# Sheet1.net
KiCad netlist of a schematic drawn in Altium Designer
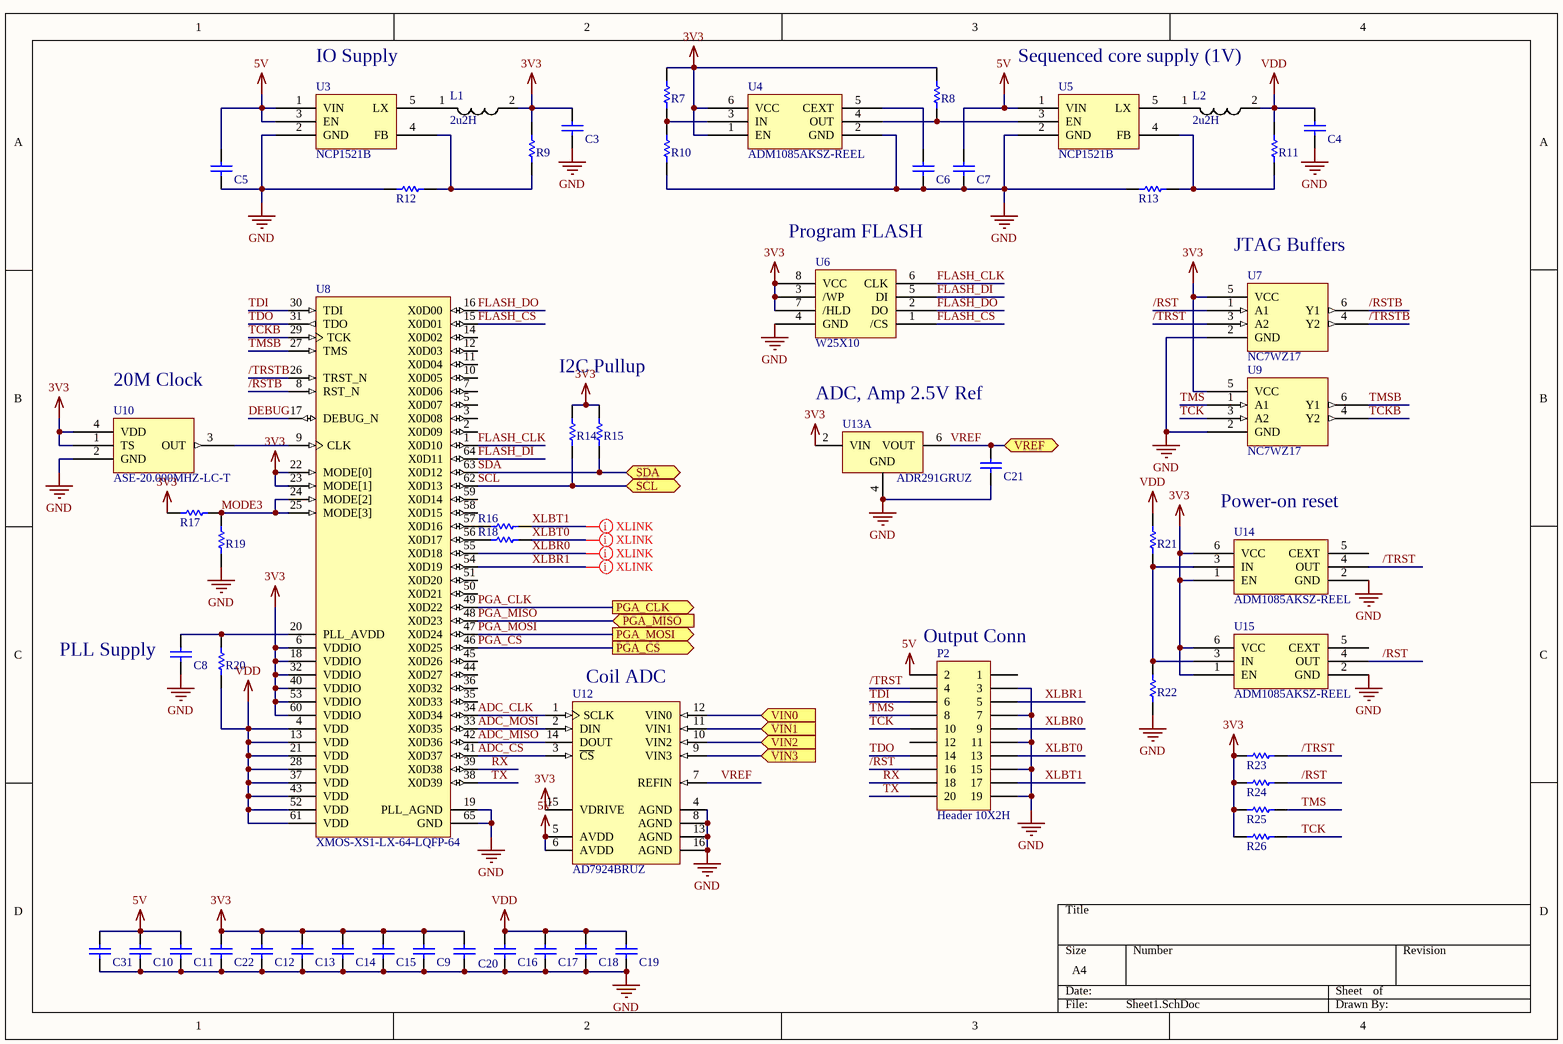
[diagram p0: Sheet1.SchDoc]

(export (version "E")
  (design (tool "Eeschema 10.0.6"))
  (components
    (comp (ref "C3")
      (value "CAP 10uF 6.3V 0603(1608)")
      (footprint "CAPC0603(1608)100_N")
      (description "CAP 10uF 6.3V ±20% 0603 (1608 Metric) Thickness 1mm SMD")
      (fields (field (name "TOLERANCE") "±20%"))
      (libsource (lib "Altium Content Vault") (part "CMP-1035-02797-1"))
    )
    (comp (ref "C4")
      (value "CAP 10uF 6.3V 0603(1608)")
      (footprint "CAPC0603(1608)100_N")
      (description "CAP 10uF 6.3V ±20% 0603 (1608 Metric) Thickness 1mm SMD")
      (fields (field (name "TOLERANCE") "±20%"))
      (libsource (lib "Altium Content Vault") (part "CMP-1035-02797-1"))
    )
    (comp (ref "C5")
      (value "CAP 10uF 6.3V 0603(1608)")
      (footprint "CAPC0603(1608)100_N")
      (description "CAP 10uF 6.3V ±20% 0603 (1608 Metric) Thickness 1mm SMD")
      (fields (field (name "TOLERANCE") "±20%"))
      (libsource (lib "Altium Content Vault") (part "CMP-1035-02797-1"))
    )
    (comp (ref "C6")
      (value "CAP 10nF 10V 0402(1005)")
      (footprint "CAPC0402(1005)60_N")
      (description "CAP 10nF 10V ±5% 0402 (1005 Metric) Thickness 0.6mm SMD")
      (fields (field (name "TOLERANCE") "±5%"))
      (libsource (lib "Altium Content Vault") (part "CMP-1034-01870-1"))
    )
    (comp (ref "C7")
      (value "CAP 10uF 6.3V 0603(1608)")
      (footprint "CAPC0603(1608)100_N")
      (description "CAP 10uF 6.3V ±20% 0603 (1608 Metric) Thickness 1mm SMD")
      (fields (field (name "TOLERANCE") "±20%"))
      (libsource (lib "Altium Content Vault") (part "CMP-1035-02797-1"))
    )
    (comp (ref "C8")
      (value "CAP 1uF 16V 0402(1005)")
      (footprint "CAPC0402(1005)60_N")
      (description "CAP 1uF 16V ±20% 0402 (1005 Metric) Thickness 0.6mm SMD")
      (fields (field (name "TOLERANCE") "±20%"))
      (libsource (lib "Altium Content Vault") (part "CMP-1034-02120-1"))
    )
    (comp (ref "C9")
      (value "CAP 100nF 25V 0402(1005)")
      (footprint "CAPC0402(1005)60_N")
      (description "CAP 100nF 25V ±20% 0402 (1005 Metric) Thickness 0.6mm SMD")
      (fields (field (name "TOLERANCE") "±20%"))
      (libsource (lib "Altium Content Vault") (part "CMP-1034-02073-1"))
    )
    (comp (ref "C10")
      (value "CAP 100nF 25V 0402(1005)")
      (footprint "CAPC0402(1005)60_N")
      (description "CAP 100nF 25V ±20% 0402 (1005 Metric) Thickness 0.6mm SMD")
      (fields (field (name "TOLERANCE") "±20%"))
      (libsource (lib "Altium Content Vault") (part "CMP-1034-02073-1"))
    )
    (comp (ref "C11")
      (value "CAP 100nF 25V 0402(1005)")
      (footprint "CAPC0402(1005)60_N")
      (description "CAP 100nF 25V ±20% 0402 (1005 Metric) Thickness 0.6mm SMD")
      (fields (field (name "TOLERANCE") "±20%"))
      (libsource (lib "Altium Content Vault") (part "CMP-1034-02073-1"))
    )
    (comp (ref "C12")
      (value "CAP 1uF 16V 0402(1005)")
      (footprint "CAPC0402(1005)60_N")
      (description "CAP 1uF 16V ±20% 0402 (1005 Metric) Thickness 0.6mm SMD")
      (fields (field (name "TOLERANCE") "±20%"))
      (libsource (lib "Altium Content Vault") (part "CMP-1034-02120-1"))
    )
    (comp (ref "C13")
      (value "CAP 1uF 16V 0402(1005)")
      (footprint "CAPC0402(1005)60_N")
      (description "CAP 1uF 16V ±20% 0402 (1005 Metric) Thickness 0.6mm SMD")
      (fields (field (name "TOLERANCE") "±20%"))
      (libsource (lib "Altium Content Vault") (part "CMP-1034-02120-1"))
    )
    (comp (ref "C14")
      (value "CAP 100nF 25V 0402(1005)")
      (footprint "CAPC0402(1005)60_N")
      (description "CAP 100nF 25V ±20% 0402 (1005 Metric) Thickness 0.6mm SMD")
      (fields (field (name "TOLERANCE") "±20%"))
      (libsource (lib "Altium Content Vault") (part "CMP-1034-02073-1"))
    )
    (comp (ref "C15")
      (value "CAP 100nF 25V 0402(1005)")
      (footprint "CAPC0402(1005)60_N")
      (description "CAP 100nF 25V ±20% 0402 (1005 Metric) Thickness 0.6mm SMD")
      (fields (field (name "TOLERANCE") "±20%"))
      (libsource (lib "Altium Content Vault") (part "CMP-1034-02073-1"))
    )
    (comp (ref "C16")
      (value "CAP 100nF 25V 0402(1005)")
      (footprint "CAPC0402(1005)60_N")
      (description "CAP 100nF 25V ±20% 0402 (1005 Metric) Thickness 0.6mm SMD")
      (fields (field (name "TOLERANCE") "±20%"))
      (libsource (lib "Altium Content Vault") (part "CMP-1034-02073-1"))
    )
    (comp (ref "C17")
      (value "CAP 100nF 25V 0402(1005)")
      (footprint "CAPC0402(1005)60_N")
      (description "CAP 100nF 25V ±20% 0402 (1005 Metric) Thickness 0.6mm SMD")
      (fields (field (name "TOLERANCE") "±20%"))
      (libsource (lib "Altium Content Vault") (part "CMP-1034-02073-1"))
    )
    (comp (ref "C18")
      (value "CAP 1uF 16V 0402(1005)")
      (footprint "CAPC0402(1005)60_N")
      (description "CAP 1uF 16V ±20% 0402 (1005 Metric) Thickness 0.6mm SMD")
      (fields (field (name "TOLERANCE") "±20%"))
      (libsource (lib "Altium Content Vault") (part "CMP-1034-02120-1"))
    )
    (comp (ref "C19")
      (value "CAP 1uF 16V 0402(1005)")
      (footprint "CAPC0402(1005)60_N")
      (description "CAP 1uF 16V ±20% 0402 (1005 Metric) Thickness 0.6mm SMD")
      (fields (field (name "TOLERANCE") "±20%"))
      (libsource (lib "Altium Content Vault") (part "CMP-1034-02120-1"))
    )
    (comp (ref "C20")
      (value "CAP 100nF 25V 0402(1005)")
      (footprint "CAPC0402(1005)60_N")
      (description "CAP 100nF 25V ±20% 0402 (1005 Metric) Thickness 0.6mm SMD")
      (fields (field (name "TOLERANCE") "±20%"))
      (libsource (lib "Altium Content Vault") (part "CMP-1034-02073-1"))
    )
    (comp (ref "C21")
      (value "CAP 100nF 25V 0402(1005)")
      (footprint "CAPC0402(1005)60_N")
      (description "CAP 100nF 25V ±20% 0402 (1005 Metric) Thickness 0.6mm SMD")
      (fields (field (name "TOLERANCE") "±20%"))
      (libsource (lib "Altium Content Vault") (part "CMP-1034-02073-1"))
    )
    (comp (ref "C22")
      (value "CAP 1uF 16V 0402(1005)")
      (footprint "CAPC0402(1005)60_N")
      (description "CAP 1uF 16V ±20% 0402 (1005 Metric) Thickness 0.6mm SMD")
      (fields (field (name "TOLERANCE") "±20%"))
      (libsource (lib "Altium Content Vault") (part "CMP-1034-02120-1"))
    )
    (comp (ref "C31")
      (value "CAP 10uF 6.3V 0603(1608)")
      (footprint "CAPC0603(1608)100_N")
      (description "CAP 10uF 6.3V ±20% 0603 (1608 Metric) Thickness 1mm SMD")
      (fields (field (name "TOLERANCE") "±20%"))
      (libsource (lib "Altium Content Vault") (part "CMP-1035-02797-1"))
    )
    (comp (ref "L1")
      (value "2u2H")
      (footprint "2016 Inductor")
      (libsource (lib "Centum") (part "2016 Inductor"))
    )
    (comp (ref "L2")
      (value "2u2H")
      (footprint "2016 Inductor")
      (libsource (lib "Centum") (part "2016 Inductor"))
    )
    (comp (ref "P2")
      (value "Header 10X2H")
      (footprint "HDR2X10H")
      (description "Header, 10-Pin, Dual row, Right Angle")
      (fields (field (name "PUBLISHER") "Altium Limited"))
      (libsource (lib "Miscellaneous Connectors") (part "Header 10X2H"))
    )
    (comp (ref "R7")
      (value "36K 1% 0402(1005)")
      (footprint "RESC0402(1005)_N")
      (description "36K 0.063W 1% 0402 (1005 Metric)  SMD")
      (fields (field (name "POWER") "0.063 W") (field (name "TOLERANCE") "1 %"))
      (libsource (lib "Altium Content Vault") (part "CMP-1011-00685-1"))
    )
    (comp (ref "R8")
      (value "10K 1% 0402(1005)")
      (footprint "RESC0402(1005)_N")
      (description "10K 0.063W 1% 0402 (1005 Metric)  SMD")
      (fields (field (name "TOLERANCE") "1 %") (field (name "POWER") "0.063 W"))
      (libsource (lib "Altium Content Vault") (part "CMP-1011-00623-1"))
    )
    (comp (ref "R9")
      (value "68K 1% 0402(1005)")
      (footprint "RESC0402(1005)_N")
      (description "68K 0.063W 1% 0402 (1005 Metric)  SMD")
      (fields (field (name "TOLERANCE") "1 %") (field (name "POWER") "0.063 W"))
      (libsource (lib "Altium Content Vault") (part "CMP-1011-00717-1"))
    )
    (comp (ref "R10")
      (value "10K 1% 0402(1005)")
      (footprint "RESC0402(1005)_N")
      (description "10K 0.063W 1% 0402 (1005 Metric)  SMD")
      (fields (field (name "TOLERANCE") "1 %") (field (name "POWER") "0.063 W"))
      (libsource (lib "Altium Content Vault") (part "CMP-1011-00623-1"))
    )
    (comp (ref "R11")
      (value "68K 1% 0402(1005)")
      (footprint "RESC0402(1005)_N")
      (description "68K 0.063W 1% 0402 (1005 Metric)  SMD")
      (fields (field (name "TOLERANCE") "1 %") (field (name "POWER") "0.063 W"))
      (libsource (lib "Altium Content Vault") (part "CMP-1011-00717-1"))
    )
    (comp (ref "R12")
      (value "15K 5% 0402(1005)")
      (footprint "RESC0402(1005)_N")
      (description "15K 0.063W 5% 0402 (1005 Metric)  SMD")
      (fields (field (name "TOLERANCE") "5 %") (field (name "POWER") "0.063 W"))
      (libsource (lib "Altium Content Vault") (part "RES"))
    )
    (comp (ref "R13")
      (value "100K 1% 0402(1005)")
      (footprint "RESC0402(1005)_N")
      (description "100K 0.063W 1% 0402 (1005 Metric)  SMD")
      (fields (field (name "POWER") "0.063 W") (field (name "TOLERANCE") "1 %"))
      (libsource (lib "Altium Content Vault") (part "CMP-1011-00736-1"))
    )
    (comp (ref "R14")
      (value "10K 1% 0402(1005)")
      (footprint "RESC0402(1005)_N")
      (description "10K 0.063W 1% 0402 (1005 Metric)  SMD")
      (fields (field (name "TOLERANCE") "1 %") (field (name "POWER") "0.063 W"))
      (libsource (lib "Altium Content Vault") (part "CMP-1011-00623-1"))
    )
    (comp (ref "R15")
      (value "10K 1% 0402(1005)")
      (footprint "RESC0402(1005)_N")
      (description "10K 0.063W 1% 0402 (1005 Metric)  SMD")
      (fields (field (name "TOLERANCE") "1 %") (field (name "POWER") "0.063 W"))
      (libsource (lib "Altium Content Vault") (part "CMP-1011-00623-1"))
    )
    (comp (ref "R16")
      (value "33R 5% 0402(1005)")
      (footprint "RESC0402(1005)_N")
      (description "33R 0.063W 5% 0402 (1005 Metric)  SMD")
      (fields (field (name "TOLERANCE") "5 %") (field (name "POWER") "0.063 W"))
      (libsource (lib "Altium Content Vault") (part "CMP-1011-00038-1"))
    )
    (comp (ref "R17")
      (value "10K 1% 0402(1005)")
      (footprint "RESC0402(1005)_N")
      (description "10K 0.063W 1% 0402 (1005 Metric)  SMD")
      (fields (field (name "TOLERANCE") "1 %") (field (name "POWER") "0.063 W"))
      (libsource (lib "Altium Content Vault") (part "CMP-1011-00623-1"))
    )
    (comp (ref "R18")
      (value "33R 5% 0402(1005)")
      (footprint "RESC0402(1005)_N")
      (description "33R 0.063W 5% 0402 (1005 Metric)  SMD")
      (fields (field (name "TOLERANCE") "5 %") (field (name "POWER") "0.063 W"))
      (libsource (lib "Altium Content Vault") (part "CMP-1011-00038-1"))
    )
    (comp (ref "R19")
      (value "Jumper 0402(1005)")
      (footprint "RESC0402(1005)_N")
      (description "Jumper 0402 (1005 Metric)")
      (fields (field (name "TOLERANCE") "None"))
      (libsource (lib "Altium Content Vault") (part "CMP-1011-00001-1"))
    )
    (comp (ref "R20")
      (value "4R7 5% 0402(1005)")
      (footprint "RESC0402(1005)_N")
      (description "4R7 0.063W 5% 0402 (1005 Metric)  SMD")
      (fields (field (name "POWER") "0.063 W") (field (name "TOLERANCE") "5 %"))
      (libsource (lib "Altium Content Vault") (part "CMP-1011-00018-1"))
    )
    (comp (ref "R21")
      (value "15K 1% 0402(1005)")
      (footprint "RESC0402(1005)_N")
      (description "15K 0.063W 1% 0402 (1005 Metric)  SMD")
      (fields (field (name "POWER") "0.063 W") (field (name "TOLERANCE") "1 %"))
      (libsource (lib "Altium Content Vault") (part "CMP-1011-00641-1"))
    )
    (comp (ref "R22")
      (value "36K 1% 0402(1005)")
      (footprint "RESC0402(1005)_N")
      (description "36K 0.063W 1% 0402 (1005 Metric)  SMD")
      (fields (field (name "POWER") "0.063 W") (field (name "TOLERANCE") "1 %"))
      (libsource (lib "Altium Content Vault") (part "CMP-1011-00685-1"))
    )
    (comp (ref "R23")
      (value "10K 1% 0402(1005)")
      (footprint "RESC0402(1005)_N")
      (description "10K 0.063W 1% 0402 (1005 Metric)  SMD")
      (fields (field (name "TOLERANCE") "1 %") (field (name "POWER") "0.063 W"))
      (libsource (lib "Altium Content Vault") (part "CMP-1011-00623-1"))
    )
    (comp (ref "R24")
      (value "10K 1% 0402(1005)")
      (footprint "RESC0402(1005)_N")
      (description "10K 0.063W 1% 0402 (1005 Metric)  SMD")
      (fields (field (name "TOLERANCE") "1 %") (field (name "POWER") "0.063 W"))
      (libsource (lib "Altium Content Vault") (part "CMP-1011-00623-1"))
    )
    (comp (ref "R25")
      (value "10K 1% 0402(1005)")
      (footprint "RESC0402(1005)_N")
      (description "10K 0.063W 1% 0402 (1005 Metric)  SMD")
      (fields (field (name "TOLERANCE") "1 %") (field (name "POWER") "0.063 W"))
      (libsource (lib "Altium Content Vault") (part "CMP-1011-00623-1"))
    )
    (comp (ref "R26")
      (value "10K 1% 0402(1005)")
      (footprint "RESC0402(1005)_N")
      (description "10K 0.063W 1% 0402 (1005 Metric)  SMD")
      (fields (field (name "TOLERANCE") "1 %") (field (name "POWER") "0.063 W"))
      (libsource (lib "Altium Content Vault") (part "CMP-1011-00623-1"))
    )
    (comp (ref "U3") (value "NCP1521B") (footprint "TSOP5") (libsource (lib "Centum") (part "NCP1521B")))
    (comp (ref "U4")
      (value "ADM1085AKSZ-REEL")
      (footprint "KS_6")
      (description "Imported")
      (libsource (lib "Centum") (part "ADM1085AKSZ-REEL"))
    )
    (comp (ref "U5") (value "NCP1521B") (footprint "TSOP5") (libsource (lib "Centum") (part "NCP1521B")))
    (comp (ref "U6") (value "W25X10") (footprint "SO8_N") (libsource (lib "Centum") (part "W25X10")))
    (comp (ref "U7") (value "NC7WZ17") (footprint "KS_6") (libsource (lib "Centum") (part "NC7WZ17")))
    (comp (ref "U8")
      (value "XMOS-XS1-LX-64-LQFP-64")
      (footprint "XMOS-LQFP-64_V_MOD")
      (libsource (lib "Centum") (part "XMOS-XS1-LX-64-LQFP-64"))
    )
    (comp (ref "U9") (value "NC7WZ17") (footprint "KS_6") (libsource (lib "Centum") (part "NC7WZ17")))
    (comp (ref "U10")
      (value "ASE-20.000MHZ-LC-T")
      (footprint "4-SMD (3.2 x 2.5mm)")
      (libsource (lib "Centum") (part "ASE-20.000MHZ-LC-T"))
    )
    (comp (ref "U12")
      (value "AD7924BRUZ")
      (footprint "RU-16_N")
      (fields (field (name "MANUFACTURER") "Analog Devices") (field (name "GENERIC PART NUMBER") "AD7924"))
      (libsource (lib "Altium Content Vault") (part "CMP-0313-02203-2"))
    )
    (comp (ref "U13")
      (value "ADR291GRUZ")
      (footprint "ADI-RU-8_N")
      (fields (field (name "MANUFACTURER") "Analog Devices"))
      (libsource (lib "Altium Content Vault") (part "CMP-0784-00483-1"))
    )
    (comp (ref "U14")
      (value "ADM1085AKSZ-REEL")
      (footprint "KS_6")
      (description "Imported")
      (libsource (lib "Centum") (part "ADM1085AKSZ-REEL"))
    )
    (comp (ref "U15")
      (value "ADM1085AKSZ-REEL")
      (footprint "KS_6")
      (description "Imported")
      (libsource (lib "Centum") (part "ADM1085AKSZ-REEL"))
    )
  )
  (nets
    (net (code "1") (name "/ADC_CLK") (class "Default")
      (node (ref "U12") (pin "1") (pinfunction "SCLK_1") (pintype "input"))
      (node (ref "U8") (pin "34") (pinfunction "X0D34_34") (pintype "bidirectional"))
    )
    (net (code "2") (name "/ADC_CS") (class "Default")
      (node (ref "U12") (pin "3") (pinfunction "~{CS}_3") (pintype "input"))
      (node (ref "U8") (pin "41") (pinfunction "X0D37_41") (pintype "bidirectional"))
    )
    (net (code "3") (name "/ADC_MISO") (class "Default")
      (node (ref "U12") (pin "14") (pinfunction "DOUT_14") (pintype "tri_state"))
      (node (ref "U8") (pin "42") (pinfunction "X0D36_42") (pintype "bidirectional"))
    )
    (net (code "4") (name "/ADC_MOSI") (class "Default")
      (node (ref "U12") (pin "2") (pinfunction "DIN_2") (pintype "input"))
      (node (ref "U8") (pin "33") (pinfunction "X0D35_33") (pintype "bidirectional"))
    )
    (net (code "5") (name "/DEBUG") (class "Default")
      (node (ref "U8") (pin "17") (pinfunction "DEBUG_N_17") (pintype "bidirectional"))
    )
    (net (code "6") (name "/FLASH_CLK") (class "Default")
      (node (ref "U6") (pin "6") (pinfunction "CLK_6") (pintype "passive"))
      (node (ref "U8") (pin "1") (pinfunction "X0D10_1") (pintype "bidirectional"))
    )
    (net (code "7") (name "/FLASH_CS") (class "Default")
      (node (ref "U6") (pin "1") (pinfunction "/CS_1") (pintype "passive"))
      (node (ref "U8") (pin "15") (pinfunction "X0D01_15") (pintype "bidirectional"))
    )
    (net (code "8") (name "/FLASH_DI") (class "Default")
      (node (ref "U6") (pin "5") (pinfunction "DI_5") (pintype "passive"))
      (node (ref "U8") (pin "64") (pinfunction "X0D11_64") (pintype "bidirectional"))
    )
    (net (code "9") (name "/FLASH_DO") (class "Default")
      (node (ref "U6") (pin "2") (pinfunction "DO_2") (pintype "passive"))
      (node (ref "U8") (pin "16") (pinfunction "X0D00_16") (pintype "bidirectional"))
    )
    (net (code "10") (name "/MODE3") (class "Default")
      (node (ref "R17") (pin "1") (pinfunction "1_1") (pintype "passive"))
      (node (ref "R19") (pin "2") (pinfunction "2_2") (pintype "passive"))
      (node (ref "U8") (pin "24") (pinfunction "MODE[2]_24") (pintype "input"))
      (node (ref "U8") (pin "25") (pinfunction "MODE[3]_25") (pintype "input"))
    )
    (net (code "11") (name "/PGA_CLK") (class "Default")
      (node (ref "U8") (pin "49") (pinfunction "X0D22_49") (pintype "bidirectional"))
    )
    (net (code "12") (name "/PGA_CS") (class "Default")
      (node (ref "U8") (pin "46") (pinfunction "X0D25_46") (pintype "bidirectional"))
    )
    (net (code "13") (name "/PGA_MISO") (class "Default")
      (node (ref "U8") (pin "48") (pinfunction "X0D23_48") (pintype "bidirectional"))
    )
    (net (code "14") (name "/PGA_MOSI") (class "Default")
      (node (ref "U8") (pin "47") (pinfunction "X0D24_47") (pintype "bidirectional"))
    )
    (net (code "15") (name "/RX") (class "Default")
      (node (ref "P2") (pin "18") (pinfunction "18_18") (pintype "passive"))
      (node (ref "U8") (pin "39") (pinfunction "X0D38_39") (pintype "bidirectional"))
    )
    (net (code "16") (name "/SCL") (class "Default")
      (node (ref "R14") (pin "1") (pinfunction "1_1") (pintype "passive"))
      (node (ref "U8") (pin "62") (pinfunction "X0D13_62") (pintype "bidirectional"))
    )
    (net (code "17") (name "/SDA") (class "Default")
      (node (ref "R15") (pin "1") (pinfunction "1_1") (pintype "passive"))
      (node (ref "U8") (pin "63") (pinfunction "X0D12_63") (pintype "bidirectional"))
    )
    (net (code "18") (name "/TCK") (class "Default")
      (node (ref "P2") (pin "10") (pinfunction "10_10") (pintype "passive"))
      (node (ref "R26") (pin "1") (pinfunction "1_1") (pintype "passive"))
      (node (ref "U9") (pin "3") (pinfunction "A2_3") (pintype "input"))
    )
    (net (code "19") (name "/TCKB") (class "Default")
      (node (ref "U8") (pin "29") (pinfunction "TCK_29") (pintype "input"))
      (node (ref "U9") (pin "4") (pinfunction "Y2_4") (pintype "output"))
    )
    (net (code "20") (name "/TDI") (class "Default")
      (node (ref "P2") (pin "6") (pinfunction "6_6") (pintype "passive"))
      (node (ref "U8") (pin "30") (pinfunction "TDI_30") (pintype "input"))
    )
    (net (code "21") (name "/TDO") (class "Default")
      (node (ref "P2") (pin "14") (pinfunction "14_14") (pintype "passive"))
      (node (ref "U8") (pin "31") (pinfunction "TDO_31") (pintype "output"))
    )
    (net (code "22") (name "/TMS") (class "Default")
      (node (ref "P2") (pin "8") (pinfunction "8_8") (pintype "passive"))
      (node (ref "R25") (pin "1") (pinfunction "1_1") (pintype "passive"))
      (node (ref "U9") (pin "1") (pinfunction "A1_1") (pintype "input"))
    )
    (net (code "23") (name "/TMSB") (class "Default")
      (node (ref "U8") (pin "27") (pinfunction "TMS_27") (pintype "input"))
      (node (ref "U9") (pin "6") (pinfunction "Y1_6") (pintype "output"))
    )
    (net (code "24") (name "/TX") (class "Default")
      (node (ref "P2") (pin "20") (pinfunction "20_20") (pintype "passive"))
      (node (ref "U8") (pin "38") (pinfunction "X0D39_38") (pintype "bidirectional"))
    )
    (net (code "25") (name "/VIN0") (class "Default")
      (node (ref "U12") (pin "12") (pinfunction "VIN0_12") (pintype "input"))
    )
    (net (code "26") (name "/VIN1") (class "Default")
      (node (ref "U12") (pin "11") (pinfunction "VIN1_11") (pintype "input"))
    )
    (net (code "27") (name "/VIN2") (class "Default")
      (node (ref "U12") (pin "10") (pinfunction "VIN2_10") (pintype "input"))
    )
    (net (code "28") (name "/VIN3") (class "Default")
      (node (ref "U12") (pin "9") (pinfunction "VIN3_9") (pintype "input"))
    )
    (net (code "29") (name "/VREF") (class "Default")
      (node (ref "C21") (pin "2") (pinfunction "2_2") (pintype "passive"))
      (node (ref "U12") (pin "7") (pinfunction "REFIN_7") (pintype "input"))
      (node (ref "U13") (pin "6") (pinfunction "VOUT_6") (pintype "power_in"))
    )
    (net (code "30") (name "/XLBR0") (class "Default")
      (node (ref "P2") (pin "9") (pinfunction "9_9") (pintype "passive"))
      (node (ref "U8") (pin "55") (pinfunction "X0D18_55") (pintype "bidirectional"))
    )
    (net (code "31") (name "/XLBR1") (class "Default")
      (node (ref "P2") (pin "5") (pinfunction "5_5") (pintype "passive"))
      (node (ref "U8") (pin "54") (pinfunction "X0D19_54") (pintype "bidirectional"))
    )
    (net (code "32") (name "/XLBT0") (class "Default")
      (node (ref "P2") (pin "13") (pinfunction "13_13") (pintype "passive"))
      (node (ref "R18") (pin "2") (pinfunction "2_2") (pintype "passive"))
    )
    (net (code "33") (name "/XLBT1") (class "Default")
      (node (ref "P2") (pin "17") (pinfunction "17_17") (pintype "passive"))
      (node (ref "R16") (pin "2") (pinfunction "2_2") (pintype "passive"))
    )
    (net (code "34") (name "/{slash}RST") (class "Default")
      (node (ref "P2") (pin "16") (pinfunction "16_16") (pintype "passive"))
      (node (ref "R24") (pin "1") (pinfunction "1_1") (pintype "passive"))
      (node (ref "U15") (pin "4") (pinfunction "OUT_4") (pintype "passive"))
      (node (ref "U7") (pin "1") (pinfunction "A1_1") (pintype "input"))
    )
    (net (code "35") (name "/{slash}RSTB") (class "Default")
      (node (ref "U7") (pin "6") (pinfunction "Y1_6") (pintype "output"))
      (node (ref "U8") (pin "8") (pinfunction "RST_N_8") (pintype "input"))
    )
    (net (code "36") (name "/{slash}TRST") (class "Default")
      (node (ref "P2") (pin "4") (pinfunction "4_4") (pintype "passive"))
      (node (ref "R23") (pin "1") (pinfunction "1_1") (pintype "passive"))
      (node (ref "U14") (pin "4") (pinfunction "OUT_4") (pintype "passive"))
      (node (ref "U7") (pin "3") (pinfunction "A2_3") (pintype "input"))
    )
    (net (code "37") (name "/{slash}TRSTB") (class "Default")
      (node (ref "U7") (pin "4") (pinfunction "Y2_4") (pintype "output"))
      (node (ref "U8") (pin "26") (pinfunction "TRST_N_26") (pintype "input"))
    )
    (net (code "38") (name "3V3") (class "Default")
      (node (ref "C12") (pin "2") (pinfunction "2_2") (pintype "passive"))
      (node (ref "C13") (pin "2") (pinfunction "2_2") (pintype "passive"))
      (node (ref "C14") (pin "2") (pinfunction "2_2") (pintype "passive"))
      (node (ref "C15") (pin "2") (pinfunction "2_2") (pintype "passive"))
      (node (ref "C20") (pin "2") (pinfunction "2_2") (pintype "passive"))
      (node (ref "C22") (pin "2") (pinfunction "2_2") (pintype "passive"))
      (node (ref "C3") (pin "2") (pinfunction "2_2") (pintype "passive"))
      (node (ref "C9") (pin "2") (pinfunction "2_2") (pintype "passive"))
      (node (ref "L1") (pin "2") (pinfunction "2_2") (pintype "passive"))
      (node (ref "R14") (pin "2") (pinfunction "2_2") (pintype "passive"))
      (node (ref "R15") (pin "2") (pinfunction "2_2") (pintype "passive"))
      (node (ref "R17") (pin "2") (pinfunction "2_2") (pintype "passive"))
      (node (ref "R23") (pin "2") (pinfunction "2_2") (pintype "passive"))
      (node (ref "R24") (pin "2") (pinfunction "2_2") (pintype "passive"))
      (node (ref "R25") (pin "2") (pinfunction "2_2") (pintype "passive"))
      (node (ref "R26") (pin "2") (pinfunction "2_2") (pintype "passive"))
      (node (ref "R7") (pin "2") (pinfunction "2_2") (pintype "passive"))
      (node (ref "R8") (pin "2") (pinfunction "2_2") (pintype "passive"))
      (node (ref "R9") (pin "2") (pinfunction "2_2") (pintype "passive"))
      (node (ref "U10") (pin "1") (pinfunction "TS_1") (pintype "passive"))
      (node (ref "U10") (pin "4") (pinfunction "VDD_4") (pintype "passive"))
      (node (ref "U12") (pin "15") (pinfunction "VDRIVE_15") (pintype "power_in"))
      (node (ref "U13") (pin "2") (pinfunction "VIN_2") (pintype "power_in"))
      (node (ref "U14") (pin "1") (pinfunction "EN_1") (pintype "passive"))
      (node (ref "U14") (pin "6") (pinfunction "VCC_6") (pintype "passive"))
      (node (ref "U15") (pin "1") (pinfunction "EN_1") (pintype "passive"))
      (node (ref "U15") (pin "6") (pinfunction "VCC_6") (pintype "passive"))
      (node (ref "U4") (pin "1") (pinfunction "EN_1") (pintype "passive"))
      (node (ref "U4") (pin "6") (pinfunction "VCC_6") (pintype "passive"))
      (node (ref "U6") (pin "3") (pinfunction "/WP_3") (pintype "passive"))
      (node (ref "U6") (pin "7") (pinfunction "/HLD_7") (pintype "passive"))
      (node (ref "U6") (pin "8") (pinfunction "VCC_8") (pintype "passive"))
      (node (ref "U7") (pin "5") (pinfunction "VCC_5") (pintype "passive"))
      (node (ref "U8") (pin "18") (pinfunction "VDDIO_18") (pintype "power_in"))
      (node (ref "U8") (pin "22") (pinfunction "MODE[0]_22") (pintype "input"))
      (node (ref "U8") (pin "23") (pinfunction "MODE[1]_23") (pintype "input"))
      (node (ref "U8") (pin "32") (pinfunction "VDDIO_32") (pintype "power_in"))
      (node (ref "U8") (pin "40") (pinfunction "VDDIO_40") (pintype "power_in"))
      (node (ref "U8") (pin "53") (pinfunction "VDDIO_53") (pintype "power_in"))
      (node (ref "U8") (pin "6") (pinfunction "VDDIO_6") (pintype "power_in"))
      (node (ref "U8") (pin "60") (pinfunction "VDDIO_60") (pintype "power_in"))
      (node (ref "U9") (pin "5") (pinfunction "VCC_5") (pintype "passive"))
    )
    (net (code "39") (name "5V") (class "Default")
      (node (ref "C10") (pin "2") (pinfunction "2_2") (pintype "passive"))
      (node (ref "C11") (pin "2") (pinfunction "2_2") (pintype "passive"))
      (node (ref "C31") (pin "1") (pinfunction "1_1") (pintype "passive"))
      (node (ref "C5") (pin "1") (pinfunction "1_1") (pintype "passive"))
      (node (ref "C7") (pin "1") (pinfunction "1_1") (pintype "passive"))
      (node (ref "P2") (pin "2") (pinfunction "2_2") (pintype "passive"))
      (node (ref "U12") (pin "5") (pinfunction "AVDD_5") (pintype "power_in"))
      (node (ref "U12") (pin "6") (pinfunction "AVDD_6") (pintype "power_in"))
      (node (ref "U3") (pin "1") (pinfunction "VIN_1") (pintype "passive"))
      (node (ref "U3") (pin "3") (pinfunction "EN_3") (pintype "passive"))
      (node (ref "U5") (pin "1") (pinfunction "VIN_1") (pintype "passive"))
    )
    (net (code "40") (name "GND") (class "Default")
      (node (ref "C10") (pin "1") (pinfunction "1_1") (pintype "passive"))
      (node (ref "C11") (pin "1") (pinfunction "1_1") (pintype "passive"))
      (node (ref "C12") (pin "1") (pinfunction "1_1") (pintype "passive"))
      (node (ref "C13") (pin "1") (pinfunction "1_1") (pintype "passive"))
      (node (ref "C14") (pin "1") (pinfunction "1_1") (pintype "passive"))
      (node (ref "C15") (pin "1") (pinfunction "1_1") (pintype "passive"))
      (node (ref "C16") (pin "1") (pinfunction "1_1") (pintype "passive"))
      (node (ref "C17") (pin "1") (pinfunction "1_1") (pintype "passive"))
      (node (ref "C18") (pin "1") (pinfunction "1_1") (pintype "passive"))
      (node (ref "C19") (pin "1") (pinfunction "1_1") (pintype "passive"))
      (node (ref "C20") (pin "1") (pinfunction "1_1") (pintype "passive"))
      (node (ref "C21") (pin "1") (pinfunction "1_1") (pintype "passive"))
      (node (ref "C22") (pin "1") (pinfunction "1_1") (pintype "passive"))
      (node (ref "C3") (pin "1") (pinfunction "1_1") (pintype "passive"))
      (node (ref "C31") (pin "2") (pinfunction "2_2") (pintype "passive"))
      (node (ref "C4") (pin "1") (pinfunction "1_1") (pintype "passive"))
      (node (ref "C5") (pin "2") (pinfunction "2_2") (pintype "passive"))
      (node (ref "C6") (pin "1") (pinfunction "1_1") (pintype "passive"))
      (node (ref "C7") (pin "2") (pinfunction "2_2") (pintype "passive"))
      (node (ref "C8") (pin "2") (pinfunction "2_2") (pintype "passive"))
      (node (ref "C9") (pin "1") (pinfunction "1_1") (pintype "passive"))
      (node (ref "P2") (pin "11") (pinfunction "11_11") (pintype "passive"))
      (node (ref "P2") (pin "15") (pinfunction "15_15") (pintype "passive"))
      (node (ref "P2") (pin "19") (pinfunction "19_19") (pintype "passive"))
      (node (ref "P2") (pin "3") (pinfunction "3_3") (pintype "passive"))
      (node (ref "P2") (pin "7") (pinfunction "7_7") (pintype "passive"))
      (node (ref "R10") (pin "1") (pinfunction "1_1") (pintype "passive"))
      (node (ref "R12") (pin "1") (pinfunction "1_1") (pintype "passive"))
      (node (ref "R13") (pin "1") (pinfunction "1_1") (pintype "passive"))
      (node (ref "R19") (pin "1") (pinfunction "1_1") (pintype "passive"))
      (node (ref "R22") (pin "1") (pinfunction "1_1") (pintype "passive"))
      (node (ref "U10") (pin "2") (pinfunction "GND_2") (pintype "passive"))
      (node (ref "U12") (pin "13") (pinfunction "AGND_13") (pintype "power_in"))
      (node (ref "U12") (pin "16") (pinfunction "AGND_16") (pintype "power_in"))
      (node (ref "U12") (pin "4") (pinfunction "AGND_4") (pintype "power_in"))
      (node (ref "U12") (pin "8") (pinfunction "AGND_8") (pintype "power_in"))
      (node (ref "U13") (pin "4") (pinfunction "GND_4") (pintype "power_in"))
      (node (ref "U14") (pin "2") (pinfunction "GND_2") (pintype "passive"))
      (node (ref "U15") (pin "2") (pinfunction "GND_2") (pintype "passive"))
      (node (ref "U3") (pin "2") (pinfunction "GND_2") (pintype "passive"))
      (node (ref "U4") (pin "2") (pinfunction "GND_2") (pintype "passive"))
      (node (ref "U5") (pin "2") (pinfunction "GND_2") (pintype "passive"))
      (node (ref "U6") (pin "4") (pinfunction "GND_4") (pintype "passive"))
      (node (ref "U7") (pin "2") (pinfunction "GND_2") (pintype "passive"))
      (node (ref "U8") (pin "19") (pinfunction "PLL_AGND_19") (pintype "power_in"))
      (node (ref "U8") (pin "65") (pinfunction "GND_65") (pintype "power_in"))
      (node (ref "U9") (pin "2") (pinfunction "GND_2") (pintype "passive"))
    )
    (net (code "41") (name "Net-(U3-FB)") (class "Default")
      (node (ref "R12") (pin "2") (pinfunction "2_2") (pintype "passive"))
      (node (ref "R9") (pin "1") (pinfunction "1_1") (pintype "passive"))
      (node (ref "U3") (pin "4") (pinfunction "FB_4") (pintype "passive"))
    )
    (net (code "42") (name "Net-(U3-LX)") (class "Default")
      (node (ref "L1") (pin "1") (pinfunction "1_1") (pintype "passive"))
      (node (ref "U3") (pin "5") (pinfunction "LX_5") (pintype "passive"))
    )
    (net (code "43") (name "Net-(U4-CEXT)") (class "Default")
      (node (ref "C6") (pin "2") (pinfunction "2_2") (pintype "passive"))
      (node (ref "U4") (pin "5") (pinfunction "CEXT_5") (pintype "passive"))
    )
    (net (code "44") (name "Net-(U4-IN)") (class "Default")
      (node (ref "R10") (pin "2") (pinfunction "2_2") (pintype "passive"))
      (node (ref "R7") (pin "1") (pinfunction "1_1") (pintype "passive"))
      (node (ref "U4") (pin "3") (pinfunction "IN_3") (pintype "passive"))
    )
    (net (code "45") (name "Net-(U4-OUT)") (class "Default")
      (node (ref "R8") (pin "1") (pinfunction "1_1") (pintype "passive"))
      (node (ref "U4") (pin "4") (pinfunction "OUT_4") (pintype "passive"))
      (node (ref "U5") (pin "3") (pinfunction "EN_3") (pintype "passive"))
    )
    (net (code "46") (name "Net-(U5-FB)") (class "Default")
      (node (ref "R11") (pin "1") (pinfunction "1_1") (pintype "passive"))
      (node (ref "R13") (pin "2") (pinfunction "2_2") (pintype "passive"))
      (node (ref "U5") (pin "4") (pinfunction "FB_4") (pintype "passive"))
    )
    (net (code "47") (name "Net-(U5-LX)") (class "Default")
      (node (ref "L2") (pin "1") (pinfunction "1_1") (pintype "passive"))
      (node (ref "U5") (pin "5") (pinfunction "LX_5") (pintype "passive"))
    )
    (net (code "48") (name "Net-(U8-PLL_AVDD)") (class "Default")
      (node (ref "C8") (pin "1") (pinfunction "1_1") (pintype "passive"))
      (node (ref "R20") (pin "2") (pinfunction "2_2") (pintype "passive"))
      (node (ref "U8") (pin "20") (pinfunction "PLL_AVDD_20") (pintype "power_in"))
    )
    (net (code "49") (name "Net-(U8-X0D16)") (class "Default")
      (node (ref "R16") (pin "1") (pinfunction "1_1") (pintype "passive"))
      (node (ref "U8") (pin "57") (pinfunction "X0D16_57") (pintype "bidirectional"))
    )
    (net (code "50") (name "Net-(U8-X0D17)") (class "Default")
      (node (ref "R18") (pin "1") (pinfunction "1_1") (pintype "passive"))
      (node (ref "U8") (pin "56") (pinfunction "X0D17_56") (pintype "bidirectional"))
    )
    (net (code "51") (name "Net-(U10-OUT)") (class "Default")
      (node (ref "U10") (pin "3") (pinfunction "OUT_3") (pintype "output"))
      (node (ref "U8") (pin "9") (pinfunction "CLK_9") (pintype "input"))
    )
    (net (code "52") (name "Net-(U14-IN)") (class "Default")
      (node (ref "R21") (pin "1") (pinfunction "1_1") (pintype "passive"))
      (node (ref "R22") (pin "2") (pinfunction "2_2") (pintype "passive"))
      (node (ref "U14") (pin "3") (pinfunction "IN_3") (pintype "passive"))
      (node (ref "U15") (pin "3") (pinfunction "IN_3") (pintype "passive"))
    )
    (net (code "53") (name "VDD") (class "Default")
      (node (ref "C16") (pin "2") (pinfunction "2_2") (pintype "passive"))
      (node (ref "C17") (pin "2") (pinfunction "2_2") (pintype "passive"))
      (node (ref "C18") (pin "2") (pinfunction "2_2") (pintype "passive"))
      (node (ref "C19") (pin "2") (pinfunction "2_2") (pintype "passive"))
      (node (ref "C4") (pin "2") (pinfunction "2_2") (pintype "passive"))
      (node (ref "L2") (pin "2") (pinfunction "2_2") (pintype "passive"))
      (node (ref "R11") (pin "2") (pinfunction "2_2") (pintype "passive"))
      (node (ref "R20") (pin "1") (pinfunction "1_1") (pintype "passive"))
      (node (ref "R21") (pin "2") (pinfunction "2_2") (pintype "passive"))
      (node (ref "U8") (pin "13") (pinfunction "VDD_13") (pintype "power_in"))
      (node (ref "U8") (pin "21") (pinfunction "VDD_21") (pintype "power_in"))
      (node (ref "U8") (pin "28") (pinfunction "VDD_28") (pintype "power_in"))
      (node (ref "U8") (pin "37") (pinfunction "VDD_37") (pintype "power_in"))
      (node (ref "U8") (pin "4") (pinfunction "VDD_4") (pintype "power_in"))
      (node (ref "U8") (pin "43") (pinfunction "VDD_43") (pintype "power_in"))
      (node (ref "U8") (pin "52") (pinfunction "VDD_52") (pintype "power_in"))
      (node (ref "U8") (pin "61") (pinfunction "VDD_61") (pintype "power_in"))
    )
    (net (code "54") (name "unconnected-(P2-Pad1)") (class "Default")
      (node (ref "P2") (pin "1") (pinfunction "1_1") (pintype "passive"))
    )
    (net (code "55") (name "unconnected-(P2-Pad12)") (class "Default")
      (node (ref "P2") (pin "12") (pinfunction "12_12") (pintype "passive"))
    )
    (net (code "56") (name "unconnected-(U8-X0D02-Pad14)") (class "Default")
      (node (ref "U8") (pin "14") (pinfunction "X0D02_14") (pintype "bidirectional"))
    )
    (net (code "57") (name "unconnected-(U8-X0D03-Pad12)") (class "Default")
      (node (ref "U8") (pin "12") (pinfunction "X0D03_12") (pintype "bidirectional"))
    )
    (net (code "58") (name "unconnected-(U8-X0D04-Pad11)") (class "Default")
      (node (ref "U8") (pin "11") (pinfunction "X0D04_11") (pintype "bidirectional"))
    )
    (net (code "59") (name "unconnected-(U8-X0D05-Pad10)") (class "Default")
      (node (ref "U8") (pin "10") (pinfunction "X0D05_10") (pintype "bidirectional"))
    )
    (net (code "60") (name "unconnected-(U8-X0D06-Pad7)") (class "Default")
      (node (ref "U8") (pin "7") (pinfunction "X0D06_7") (pintype "bidirectional"))
    )
    (net (code "61") (name "unconnected-(U8-X0D07-Pad5)") (class "Default")
      (node (ref "U8") (pin "5") (pinfunction "X0D07_5") (pintype "bidirectional"))
    )
    (net (code "62") (name "unconnected-(U8-X0D08-Pad3)") (class "Default")
      (node (ref "U8") (pin "3") (pinfunction "X0D08_3") (pintype "bidirectional"))
    )
    (net (code "63") (name "unconnected-(U8-X0D09-Pad2)") (class "Default")
      (node (ref "U8") (pin "2") (pinfunction "X0D09_2") (pintype "bidirectional"))
    )
    (net (code "64") (name "unconnected-(U8-X0D14-Pad59)") (class "Default")
      (node (ref "U8") (pin "59") (pinfunction "X0D14_59") (pintype "bidirectional"))
    )
    (net (code "65") (name "unconnected-(U8-X0D15-Pad58)") (class "Default")
      (node (ref "U8") (pin "58") (pinfunction "X0D15_58") (pintype "bidirectional"))
    )
    (net (code "66") (name "unconnected-(U8-X0D20-Pad51)") (class "Default")
      (node (ref "U8") (pin "51") (pinfunction "X0D20_51") (pintype "bidirectional"))
    )
    (net (code "67") (name "unconnected-(U8-X0D21-Pad50)") (class "Default")
      (node (ref "U8") (pin "50") (pinfunction "X0D21_50") (pintype "bidirectional"))
    )
    (net (code "68") (name "unconnected-(U8-X0D26-Pad45)") (class "Default")
      (node (ref "U8") (pin "45") (pinfunction "X0D26_45") (pintype "bidirectional"))
    )
    (net (code "69") (name "unconnected-(U8-X0D27-Pad44)") (class "Default")
      (node (ref "U8") (pin "44") (pinfunction "X0D27_44") (pintype "bidirectional"))
    )
    (net (code "70") (name "unconnected-(U8-X0D32-Pad36)") (class "Default")
      (node (ref "U8") (pin "36") (pinfunction "X0D32_36") (pintype "bidirectional"))
    )
    (net (code "71") (name "unconnected-(U8-X0D33-Pad35)") (class "Default")
      (node (ref "U8") (pin "35") (pinfunction "X0D33_35") (pintype "bidirectional"))
    )
    (net (code "72") (name "unconnected-(U14-CEXT-Pad5)") (class "Default")
      (node (ref "U14") (pin "5") (pinfunction "CEXT_5") (pintype "passive"))
    )
    (net (code "73") (name "unconnected-(U15-CEXT-Pad5)") (class "Default")
      (node (ref "U15") (pin "5") (pinfunction "CEXT_5") (pintype "passive"))
    )
  )
)
